# garden_box.net
KiCad netlist of a schematic drawn in EAGLE
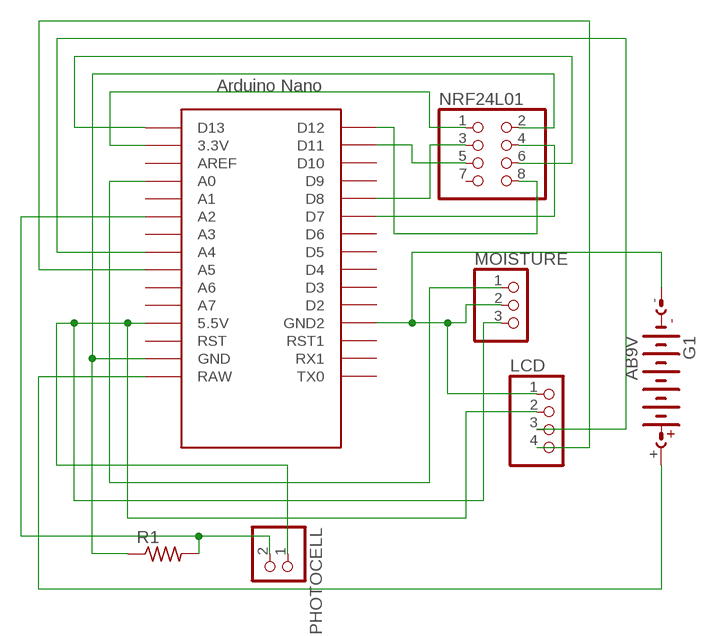
[diagram p0: schematic, sheet 1]

(export (version "E")
  (design (tool "Eeschema 10.0.6"))
  (components
    (comp (ref "G1")
      (value "AB9V")
      (footprint "eagle-import:AB9V")
      (libsource (lib "eagle-import") (part "AB9V"))
    )
    (comp (ref "LCD")
      (value "PINHD-1X4")
      (footprint "eagle-import:1X04")
      (libsource (lib "eagle-import") (part "PINHD-1X4"))
    )
    (comp (ref "MOISTURE")
      (value "PINHD-1X3")
      (footprint "eagle-import:1X03")
      (libsource (lib "eagle-import") (part "PINHD-1X3"))
    )
    (comp (ref "NRF24L01")
      (value "PINHD-2X4")
      (footprint "eagle-import:2X04")
      (libsource (lib "eagle-import") (part "PINHD-2X4"))
    )
    (comp (ref "PHOTOCELL")
      (value "PINHD-1X2")
      (footprint "eagle-import:1X02")
      (libsource (lib "eagle-import") (part "PINHD-1X2"))
    )
    (comp (ref "R1")
      (value "R-US_0204/7")
      (footprint "eagle-import:0204_7")
      (libsource (lib "eagle-import") (part "R-US_0204/7"))
    )
    (comp (ref "U$1")
      (value "NANO")
      (footprint "eagle-import:NANO")
      (libsource (lib "eagle-import") (part "NANO"))
    )
  )
  (nets
    (net (code "1") (name "Net-(G1-Pad+)") (class "Default")
      (node (ref "G1") (pin "+") (pinfunction "+_+") (pintype "passive"))
      (node (ref "U$1") (pin "RAW") (pinfunction "RAW_RAW") (pintype "bidirectional"))
    )
    (net (code "2") (name "Net-(LCD-Pad3)") (class "Default")
      (node (ref "LCD") (pin "3") (pinfunction "3_3") (pintype "passive"))
      (node (ref "U$1") (pin "A4") (pinfunction "A4_A4") (pintype "bidirectional"))
    )
    (net (code "3") (name "Net-(LCD-Pad4)") (class "Default")
      (node (ref "LCD") (pin "4") (pinfunction "4_4") (pintype "passive"))
      (node (ref "U$1") (pin "A5") (pinfunction "A5_A5") (pintype "bidirectional"))
    )
    (net (code "4") (name "Net-(MOISTURE-Pad1)") (class "Default")
      (node (ref "MOISTURE") (pin "1") (pinfunction "1_1") (pintype "passive"))
      (node (ref "U$1") (pin "A0") (pinfunction "A0_A0") (pintype "bidirectional"))
    )
    (net (code "5") (name "Net-(NRF24L01-Pad1)") (class "Default")
      (node (ref "NRF24L01") (pin "1") (pinfunction "1_1") (pintype "passive"))
      (node (ref "U$1") (pin "3.3V") (pinfunction "3.3V_3.3V") (pintype "bidirectional"))
    )
    (net (code "6") (name "Net-(NRF24L01-Pad2)") (class "Default")
      (node (ref "NRF24L01") (pin "2") (pinfunction "2_2") (pintype "passive"))
      (node (ref "R1") (pin "1") (pinfunction "1_1") (pintype "passive"))
      (node (ref "U$1") (pin "GND") (pinfunction "GND_GND") (pintype "bidirectional"))
    )
    (net (code "7") (name "Net-(NRF24L01-Pad3)") (class "Default")
      (node (ref "NRF24L01") (pin "3") (pinfunction "3_3") (pintype "passive"))
      (node (ref "U$1") (pin "D8") (pinfunction "D8_D8") (pintype "bidirectional"))
    )
    (net (code "8") (name "Net-(NRF24L01-Pad4)") (class "Default")
      (node (ref "NRF24L01") (pin "4") (pinfunction "4_4") (pintype "passive"))
      (node (ref "U$1") (pin "D7") (pinfunction "D7_D7") (pintype "bidirectional"))
    )
    (net (code "9") (name "Net-(NRF24L01-Pad5)") (class "Default")
      (node (ref "NRF24L01") (pin "5") (pinfunction "5_5") (pintype "passive"))
      (node (ref "U$1") (pin "D11") (pinfunction "D11_D11") (pintype "bidirectional"))
    )
    (net (code "10") (name "Net-(NRF24L01-Pad6)") (class "Default")
      (node (ref "NRF24L01") (pin "6") (pinfunction "6_6") (pintype "passive"))
      (node (ref "U$1") (pin "D13") (pinfunction "D13_D13") (pintype "bidirectional"))
    )
    (net (code "11") (name "Net-(NRF24L01-Pad8)") (class "Default")
      (node (ref "NRF24L01") (pin "8") (pinfunction "8_8") (pintype "passive"))
      (node (ref "U$1") (pin "D12") (pinfunction "D12_D12") (pintype "bidirectional"))
    )
    (net (code "12") (name "Net-(PHOTOCELL-Pad2)") (class "Default")
      (node (ref "PHOTOCELL") (pin "2") (pinfunction "2_2") (pintype "passive"))
      (node (ref "R1") (pin "2") (pinfunction "2_2") (pintype "passive"))
      (node (ref "U$1") (pin "A2") (pinfunction "A2_A2") (pintype "bidirectional"))
    )
    (net (code "13") (name "Net-(U$1-5.5V)") (class "Default")
      (node (ref "LCD") (pin "2") (pinfunction "2_2") (pintype "passive"))
      (node (ref "MOISTURE") (pin "3") (pinfunction "3_3") (pintype "passive"))
      (node (ref "PHOTOCELL") (pin "1") (pinfunction "1_1") (pintype "passive"))
      (node (ref "U$1") (pin "5V") (pinfunction "5.5V_5V") (pintype "bidirectional"))
    )
    (net (code "14") (name "Net-(U$1-GND2)") (class "Default")
      (node (ref "G1") (pin "-") (pinfunction "-_-") (pintype "passive"))
      (node (ref "LCD") (pin "1") (pinfunction "1_1") (pintype "passive"))
      (node (ref "MOISTURE") (pin "2") (pinfunction "2_2") (pintype "passive"))
      (node (ref "U$1") (pin "GND1") (pinfunction "GND2_GND1") (pintype "bidirectional"))
    )
    (net (code "15") (name "unconnected-(NRF24L01-Pad7)") (class "Default")
      (node (ref "NRF24L01") (pin "7") (pinfunction "7_7") (pintype "passive"))
    )
    (net (code "16") (name "unconnected-(U$1-PadA1)") (class "Default")
      (node (ref "U$1") (pin "A1") (pinfunction "A1_A1") (pintype "bidirectional"))
    )
    (net (code "17") (name "unconnected-(U$1-PadA3)") (class "Default")
      (node (ref "U$1") (pin "A3") (pinfunction "A3_A3") (pintype "bidirectional"))
    )
    (net (code "18") (name "unconnected-(U$1-PadA6)") (class "Default")
      (node (ref "U$1") (pin "A6") (pinfunction "A6_A6") (pintype "bidirectional"))
    )
    (net (code "19") (name "unconnected-(U$1-PadA7)") (class "Default")
      (node (ref "U$1") (pin "A7") (pinfunction "A7_A7") (pintype "bidirectional"))
    )
    (net (code "20") (name "unconnected-(U$1-PadAREF)") (class "Default")
      (node (ref "U$1") (pin "AREF") (pinfunction "AREF_AREF") (pintype "bidirectional"))
    )
    (net (code "21") (name "unconnected-(U$1-PadD2)") (class "Default")
      (node (ref "U$1") (pin "D2") (pinfunction "D2_D2") (pintype "bidirectional"))
    )
    (net (code "22") (name "unconnected-(U$1-PadD3)") (class "Default")
      (node (ref "U$1") (pin "D3") (pinfunction "D3_D3") (pintype "bidirectional"))
    )
    (net (code "23") (name "unconnected-(U$1-PadD4)") (class "Default")
      (node (ref "U$1") (pin "D4") (pinfunction "D4_D4") (pintype "bidirectional"))
    )
    (net (code "24") (name "unconnected-(U$1-PadD5)") (class "Default")
      (node (ref "U$1") (pin "D5") (pinfunction "D5_D5") (pintype "bidirectional"))
    )
    (net (code "25") (name "unconnected-(U$1-PadD6)") (class "Default")
      (node (ref "U$1") (pin "D6") (pinfunction "D6_D6") (pintype "bidirectional"))
    )
    (net (code "26") (name "unconnected-(U$1-PadD9)") (class "Default")
      (node (ref "U$1") (pin "D9") (pinfunction "D9_D9") (pintype "bidirectional"))
    )
    (net (code "27") (name "unconnected-(U$1-PadD10)") (class "Default")
      (node (ref "U$1") (pin "D10") (pinfunction "D10_D10") (pintype "bidirectional"))
    )
    (net (code "28") (name "unconnected-(U$1-PadICSP1)") (class "Default")
      (node (ref "U$1") (pin "ICSP1") (pinfunction "ICSP1_ICSP1") (pintype "bidirectional"))
    )
    (net (code "29") (name "unconnected-(U$1-PadICSP2)") (class "Default")
      (node (ref "U$1") (pin "ICSP2") (pinfunction "ICSP2_ICSP2") (pintype "bidirectional"))
    )
    (net (code "30") (name "unconnected-(U$1-PadICSP3)") (class "Default")
      (node (ref "U$1") (pin "ICSP3") (pinfunction "ICSP3_ICSP3") (pintype "bidirectional"))
    )
    (net (code "31") (name "unconnected-(U$1-PadICSP4)") (class "Default")
      (node (ref "U$1") (pin "ICSP4") (pinfunction "ICSP4_ICSP4") (pintype "bidirectional"))
    )
    (net (code "32") (name "unconnected-(U$1-PadICSP5)") (class "Default")
      (node (ref "U$1") (pin "ICSP5") (pinfunction "ICSP5_ICSP5") (pintype "bidirectional"))
    )
    (net (code "33") (name "unconnected-(U$1-PadICSP6)") (class "Default")
      (node (ref "U$1") (pin "ICSP6") (pinfunction "ICSP6_ICSP6") (pintype "bidirectional"))
    )
    (net (code "34") (name "unconnected-(U$1-PadRST)") (class "Default")
      (node (ref "U$1") (pin "RST") (pinfunction "RST_RST") (pintype "bidirectional"))
    )
    (net (code "35") (name "unconnected-(U$1-PadRST1)") (class "Default")
      (node (ref "U$1") (pin "RST1") (pinfunction "RST1_RST1") (pintype "bidirectional"))
    )
    (net (code "36") (name "unconnected-(U$1-PadRX1)") (class "Default")
      (node (ref "U$1") (pin "RX1") (pinfunction "RX1_RX1") (pintype "bidirectional"))
    )
    (net (code "37") (name "unconnected-(U$1-PadTX0)") (class "Default")
      (node (ref "U$1") (pin "TX0") (pinfunction "TX0_TX0") (pintype "bidirectional"))
    )
  )
)
